# Morpheus_IMU.net
KiCad netlist of a schematic drawn in Altium Designer
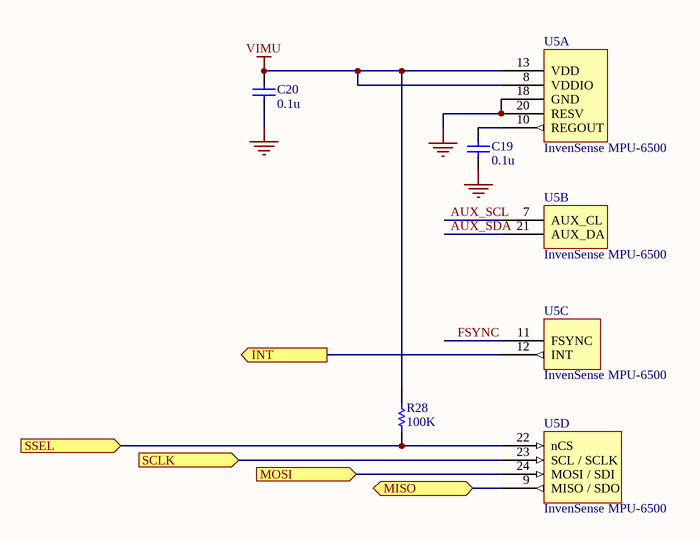
[diagram p0: Morpheus_IMU.SchDoc]

(export (version "E")
  (design (tool "Eeschema 10.0.6"))
  (components
    (comp (ref "C19")
      (value "0.1u")
      (footprint "CAP0402")
      (description "Chip capacitor")
      (fields (field (name "TOLERANCE") "10%") (field (name "VOLTAGE") "50V"))
      (libsource (lib "Hello") (part "C_0.1u_10_50_X7R_0402"))
    )
    (comp (ref "C20")
      (value "0.1u")
      (footprint "CAP0402")
      (description "Chip capacitor")
      (fields (field (name "TOLERANCE") "10%") (field (name "VOLTAGE") "50V"))
      (libsource (lib "Hello") (part "C_0.1u_10_50_X7R_0402"))
    )
    (comp (ref "R28")
      (value "100K")
      (footprint "RES0402")
      (description "Chip Resistor")
      (fields (field (name "TOLERANCE") "5 %") (field (name "POWER") "0.1 W"))
      (libsource (lib "Hello") (part "R_100K_5_0.1_0402"))
    )
    (comp (ref "U5")
      (value "InvenSense MPU-6500")
      (footprint "QFN-24")
      (description "InvenSense MPU-6500 6-axis accelerometer and gyroscope")
      (libsource (lib "Hello") (part "MPU-6500"))
    )
  )
  (nets
    (net (code "1") (name "/AUX_SCL") (class "Default")
      (node (ref "U5") (pin "7") (pinfunction "AUX_CL_7") (pintype "passive"))
    )
    (net (code "2") (name "/AUX_SDA") (class "Default")
      (node (ref "U5") (pin "21") (pinfunction "AUX_DA_21") (pintype "passive"))
    )
    (net (code "3") (name "/FSYNC") (class "Default")
      (node (ref "U5") (pin "11") (pinfunction "FSYNC_11") (pintype "input"))
    )
    (net (code "4") (name "/INT") (class "Default")
      (node (ref "U5") (pin "12") (pinfunction "INT_12") (pintype "output"))
    )
    (net (code "5") (name "/MISO") (class "Default")
      (node (ref "U5") (pin "9") (pinfunction "MISO_/_SDO_9") (pintype "output"))
    )
    (net (code "6") (name "/MOSI") (class "Default")
      (node (ref "U5") (pin "24") (pinfunction "MOSI_/_SDI_24") (pintype "input"))
    )
    (net (code "7") (name "/SCLK") (class "Default")
      (node (ref "U5") (pin "23") (pinfunction "SCL_/_SCLK_23") (pintype "input"))
    )
    (net (code "8") (name "/SSEL") (class "Default")
      (node (ref "R28") (pin "1") (pinfunction "1_1") (pintype "passive"))
      (node (ref "U5") (pin "22") (pinfunction "nCS_22") (pintype "input"))
    )
    (net (code "9") (name "GND") (class "Default")
      (node (ref "C19") (pin "1") (pinfunction "1_1") (pintype "passive"))
      (node (ref "C20") (pin "1") (pinfunction "1_1") (pintype "passive"))
      (node (ref "U5") (pin "18") (pinfunction "GND_18") (pintype "power_in"))
      (node (ref "U5") (pin "20") (pinfunction "RESV_20") (pintype "passive"))
    )
    (net (code "10") (name "Net-(U5A-REGOUT)") (class "Default")
      (node (ref "C19") (pin "2") (pinfunction "2_2") (pintype "passive"))
      (node (ref "U5") (pin "10") (pinfunction "REGOUT_10") (pintype "output"))
    )
    (net (code "11") (name "VIMU") (class "Default")
      (node (ref "C20") (pin "2") (pinfunction "2_2") (pintype "passive"))
      (node (ref "R28") (pin "2") (pinfunction "2_2") (pintype "passive"))
      (node (ref "U5") (pin "13") (pinfunction "VDD_13") (pintype "power_in"))
      (node (ref "U5") (pin "8") (pinfunction "VDDIO_8") (pintype "power_in"))
    )
  )
)
